# SolenoidStandalone.net
KiCad netlist of a schematic drawn in EAGLE
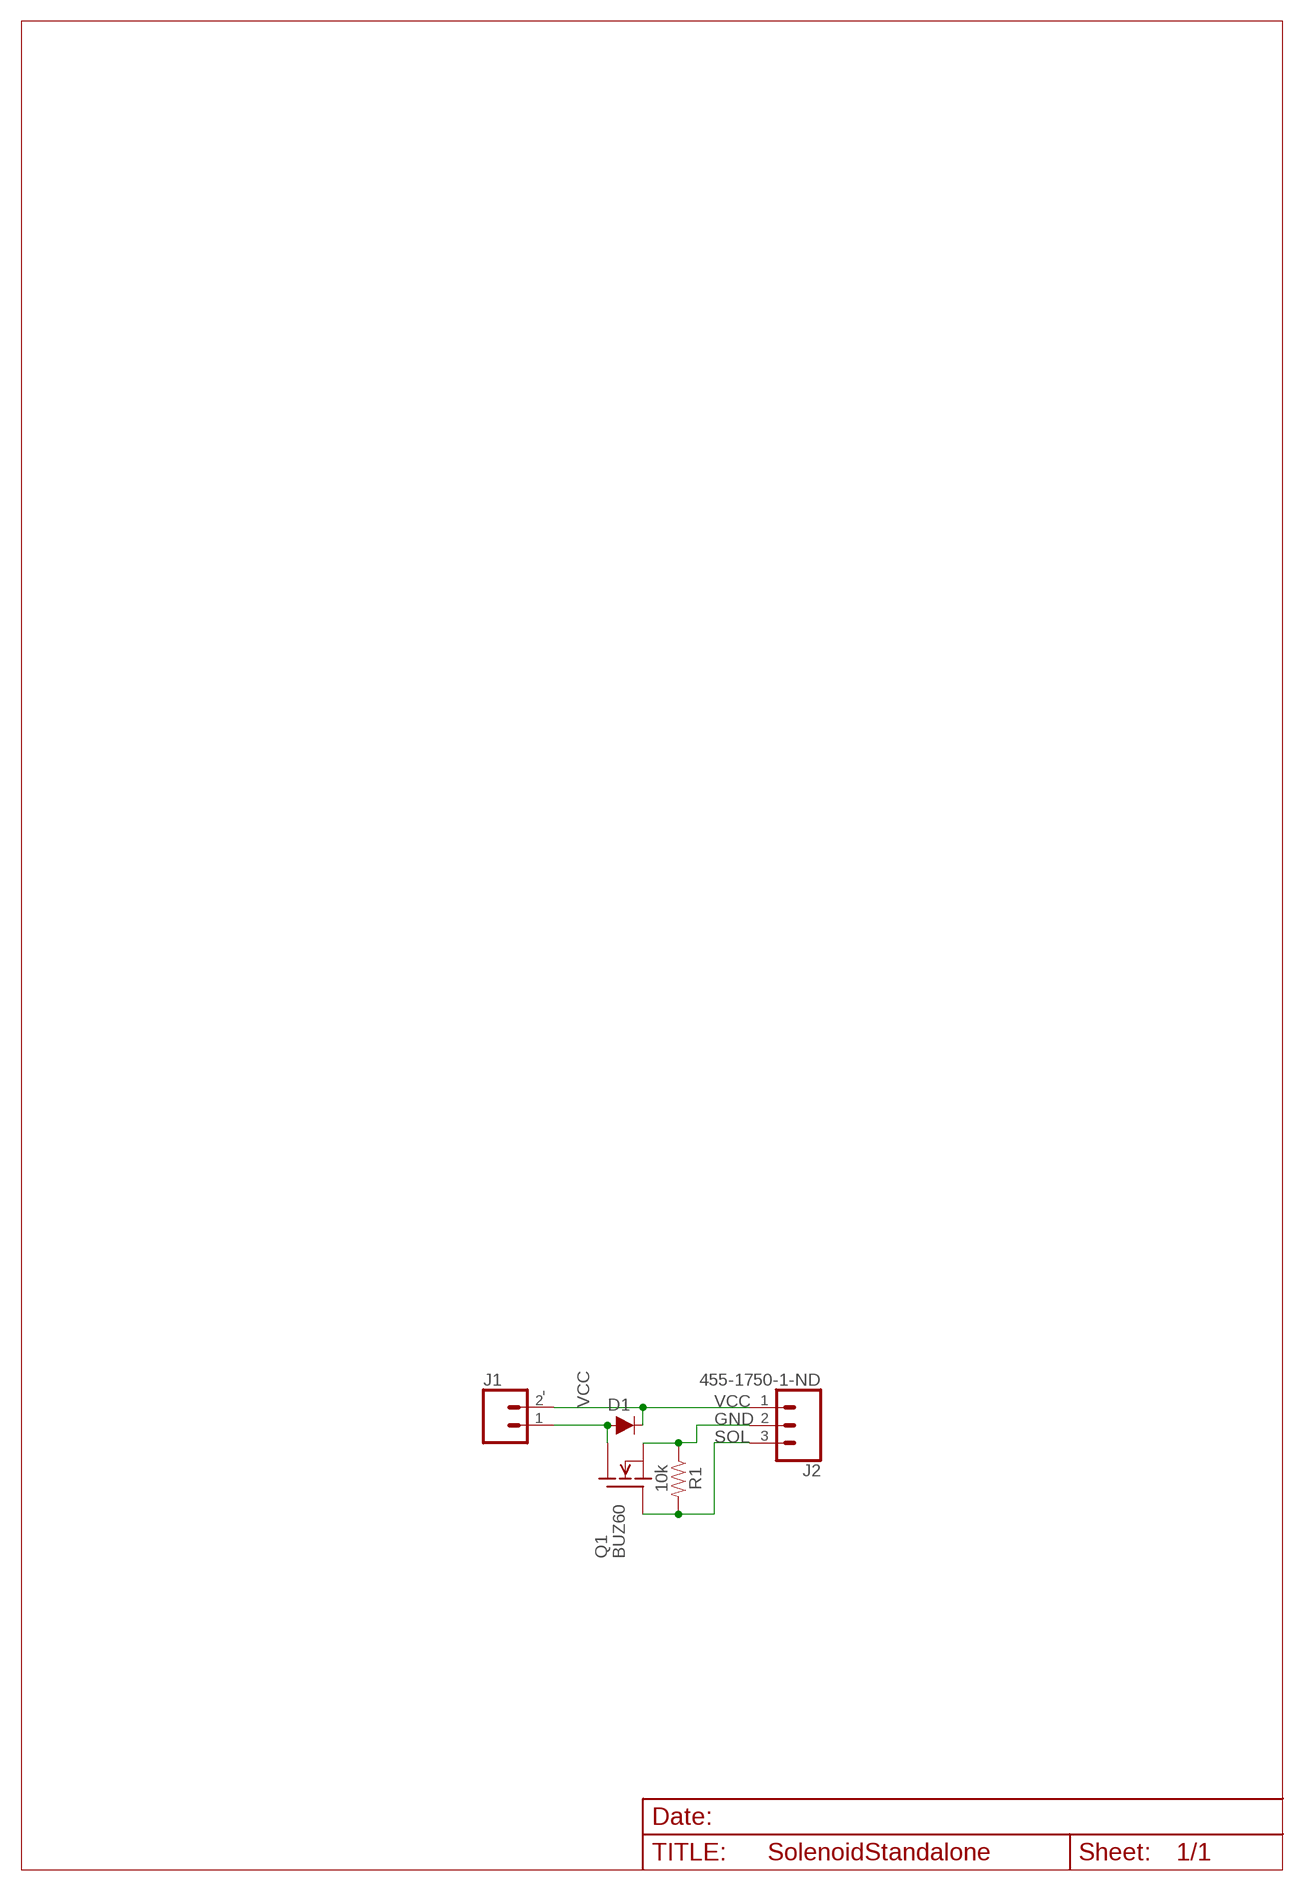
[diagram p0: schematic, sheet 1]

(export (version "E")
  (design (tool "Eeschema 10.0.6"))
  (components
    (comp (ref "D1")
      (value "200mA/100V/1V")
      (footprint "eagle-import:DIODE-1N4148")
      (libsource (lib "eagle-import") (part "DIODE-1N4148"))
    )
    (comp (ref "J1")
      (value "CONN_02")
      (footprint "eagle-import:1X02")
      (libsource (lib "eagle-import") (part "CONN_02"))
    )
    (comp (ref "J2")
      (value "455-1750-1-ND")
      (footprint "eagle-import:1X03")
      (libsource (lib "eagle-import") (part "CONN_03"))
    )
    (comp (ref "Q1")
      (value "BUZ60")
      (footprint "eagle-import:TO220")
      (libsource (lib "eagle-import") (part "BUZ60"))
    )
    (comp (ref "R1")
      (value "10k")
      (footprint "eagle-import:AXIAL-0.3")
      (libsource (lib "eagle-import") (part "RESISTORAXIAL-0.3"))
    )
  )
  (nets
    (net (code "1") (name "/-") (class "Default")
      (node (ref "D1") (pin "A") (pinfunction "A_A") (pintype "passive"))
      (node (ref "J1") (pin "1") (pinfunction "1_1") (pintype "passive"))
      (node (ref "Q1") (pin "2") (pinfunction "D_2") (pintype "passive"))
    )
    (net (code "2") (name "/GND") (class "Default")
      (node (ref "J2") (pin "2") (pinfunction "2_2") (pintype "passive"))
      (node (ref "Q1") (pin "3") (pinfunction "S_3") (pintype "passive"))
      (node (ref "R1") (pin "P$1") (pinfunction "1_P$1") (pintype "passive"))
    )
    (net (code "3") (name "/SOL") (class "Default")
      (node (ref "J2") (pin "3") (pinfunction "3_3") (pintype "passive"))
      (node (ref "Q1") (pin "1") (pinfunction "G_1") (pintype "passive"))
      (node (ref "R1") (pin "P$2") (pinfunction "2_P$2") (pintype "passive"))
    )
    (net (code "4") (name "/VCC") (class "Default")
      (node (ref "D1") (pin "C") (pinfunction "C_C") (pintype "passive"))
      (node (ref "J1") (pin "2") (pinfunction "2_2") (pintype "passive"))
      (node (ref "J2") (pin "1") (pinfunction "1_1") (pintype "passive"))
    )
  )
)
